# WirelessEarBuds_Amp.net
KiCad netlist of a schematic drawn in Altium Designer
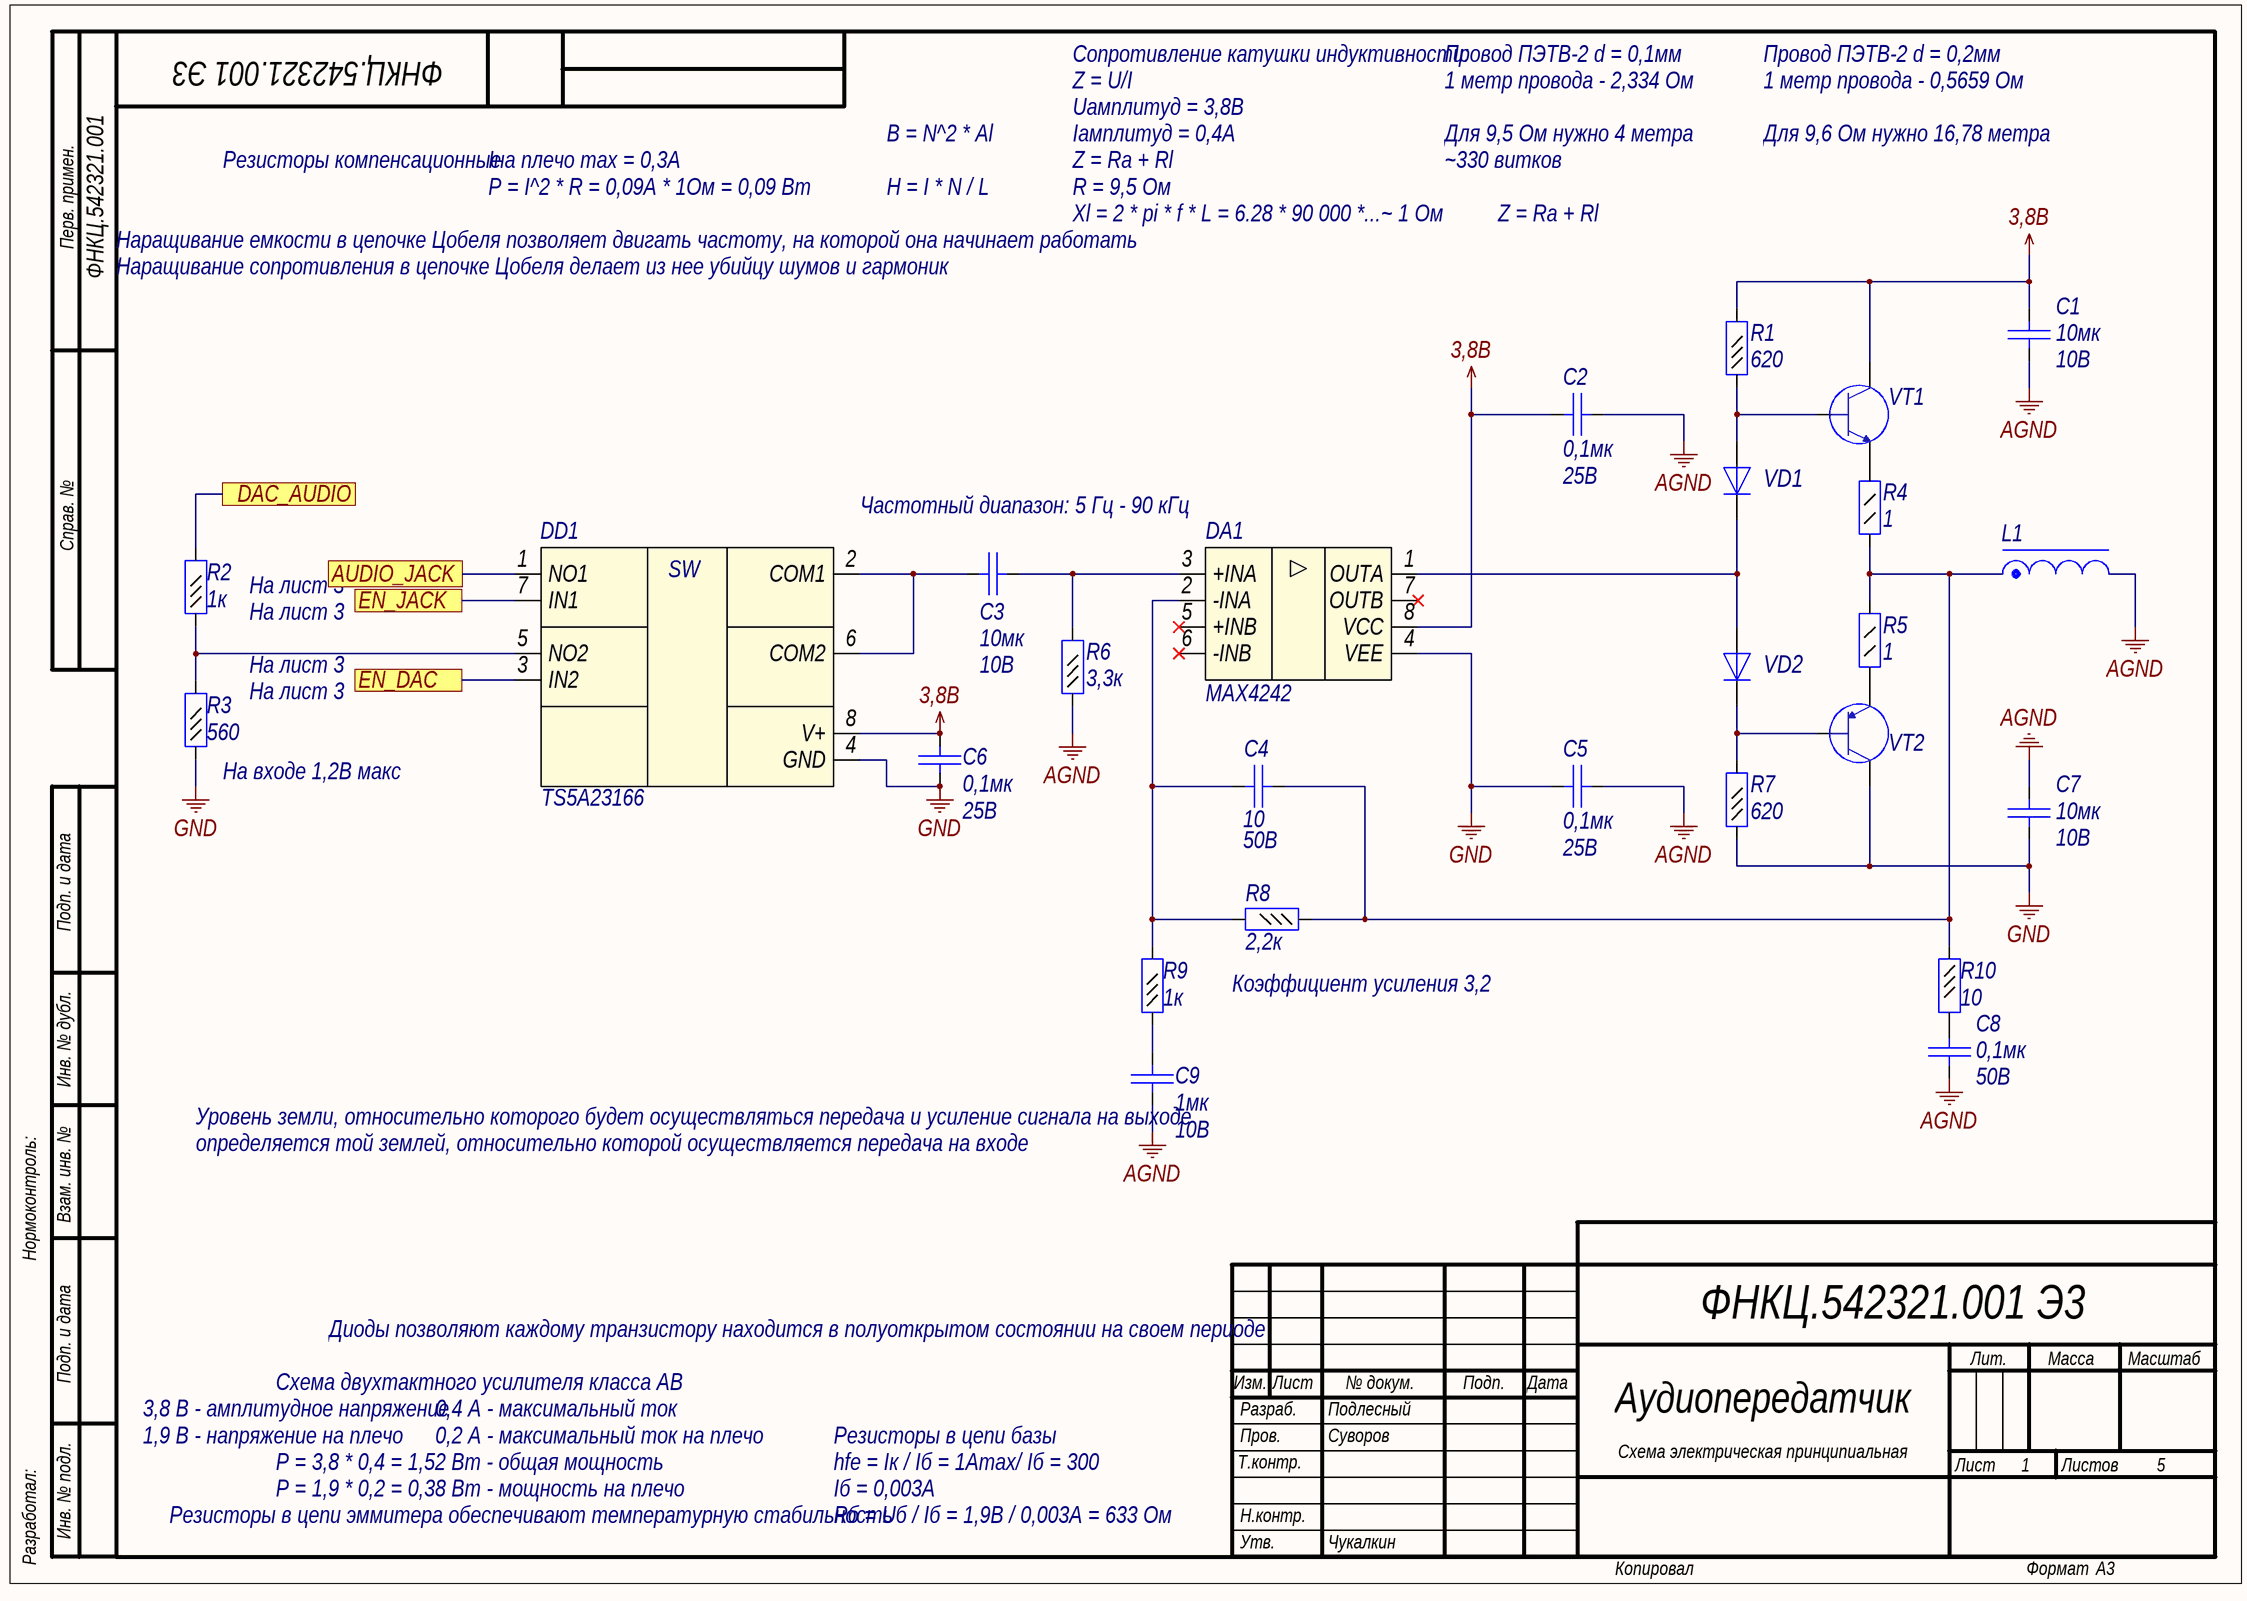
[diagram p0: WirelessEarBuds_Amp.SchDoc]

(export (version "E")
  (design (tool "Eeschema 10.0.6"))
  (components
    (comp (ref "C1")
      (value "10мк")
      (footprint "C0805")
      (description "Конденсатор")
      (fields
        (field (name "VOLTAGE") "10В")
        (field (name "PART NUMBER") "GRM21BR71A106KE51L")
        (field (name "Comment") "Capacitor")
      )
      (libsource (lib "MOP44") (part "Capacitor"))
    )
    (comp (ref "C2")
      (value "0,1мк")
      (footprint "C0402")
      (description "Конденсатор")
      (fields
        (field (name "VOLTAGE") "25B")
        (field (name "PART NUMBER") "GRM155F51E104Z**")
        (field (name "Comment") "Capacitor")
      )
      (libsource (lib "MOP44") (part "Capacitor"))
    )
    (comp (ref "C3")
      (value "10мк")
      (footprint "C0805")
      (description "Конденсатор")
      (fields
        (field (name "VOLTAGE") "10В")
        (field (name "PART NUMBER") "GRM21BR71A106KE51L")
        (field (name "Comment") "Capacitor")
      )
      (libsource (lib "MOP44") (part "Capacitor"))
    )
    (comp (ref "C4")
      (value "10")
      (footprint "C0402")
      (description "Конденсатор")
      (fields
        (field (name "VOLTAGE") "50B")
        (field (name "PART NUMBER") "GRM1535C1H100J")
        (field (name "Comment") "Capacitor")
      )
      (libsource (lib "MOP44") (part "Capacitor"))
    )
    (comp (ref "C5")
      (value "0,1мк")
      (footprint "C0402")
      (description "Конденсатор")
      (fields
        (field (name "VOLTAGE") "25B")
        (field (name "PART NUMBER") "GRM155F51E104Z**")
        (field (name "Comment") "Capacitor")
      )
      (libsource (lib "MOP44") (part "Capacitor"))
    )
    (comp (ref "C6")
      (value "0,1мк")
      (footprint "C0402")
      (description "Конденсатор")
      (fields
        (field (name "VOLTAGE") "25B")
        (field (name "PART NUMBER") "GRM155F51E104Z**")
        (field (name "Comment") "Capacitor")
      )
      (libsource (lib "MOP44") (part "Capacitor"))
    )
    (comp (ref "C7")
      (value "10мк")
      (footprint "C0805")
      (description "Конденсатор")
      (fields
        (field (name "VOLTAGE") "10В")
        (field (name "PART NUMBER") "GRM21BR71A106KE51L")
        (field (name "Comment") "Capacitor")
      )
      (libsource (lib "MOP44") (part "Capacitor"))
    )
    (comp (ref "C8")
      (value "0,1мк")
      (footprint "C0402")
      (description "Конденсатор")
      (fields
        (field (name "VOLTAGE") "50B")
        (field (name "PART NUMBER") "GRM1535C1H100J")
        (field (name "Comment") "Capacitor")
      )
      (libsource (lib "MOP44") (part "Capacitor"))
    )
    (comp (ref "C9")
      (value "1мк")
      (footprint "C0402")
      (description "Конденсатор")
      (fields
        (field (name "VOLTAGE") "10B")
        (field (name "PART NUMBER") "GRM155R61A105K")
        (field (name "Comment") "Capacitor")
      )
      (libsource (lib "MOP44") (part "Capacitor"))
    )
    (comp (ref "DA1")
      (value "MAX4242")
      (footprint "8µMAX")
      (description "МИКРОМОЩНЫЙ Single/Dual/Quad, +1.8V/10µA, SOT23,  Beyond-the-Rails Op Amps")
      (fields (field (name "PART NUMBER") "MAX4242EUA"))
      (libsource (lib "MOP44") (part "MAX4242"))
    )
    (comp (ref "DD1")
      (value "TS5A23166")
      (footprint "US8")
      (description "Dual-SPST Analog Switch")
      (libsource (lib "MOP44") (part "TS5A23166"))
    )
    (comp (ref "L1")
      (value "InductorSerd")
      (footprint "InductorPetlya")
      (description "EMI Suppression Filter")
      (libsource (lib "MOP44") (part "InductorSerd"))
    )
    (comp (ref "R1")
      (value "620")
      (footprint "R0402")
      (description "Резистор")
      (fields (field (name "PART NUMBER") "RC0402FR-07620RL") (field (name "POWER") "0,062Вт"))
      (libsource (lib "MOP44") (part "Resistor_0,062Вт"))
    )
    (comp (ref "R2")
      (value "1к")
      (footprint "R0402")
      (description "Резистор")
      (fields (field (name "PART NUMBER") "RC0402FR-072K3") (field (name "POWER") "0,062Вт"))
      (libsource (lib "MOP44") (part "Resistor_0,062Вт"))
    )
    (comp (ref "R3")
      (value "560")
      (footprint "R0402")
      (description "Резистор")
      (fields (field (name "PART NUMBER") "RC0402FR-072K3") (field (name "POWER") "0,062Вт"))
      (libsource (lib "MOP44") (part "Resistor_0,062Вт"))
    )
    (comp (ref "R4")
      (value "1")
      (footprint "R0805")
      (description "Резистор")
      (fields (field (name "PART NUMBER") "RC0805FR-071RL") (field (name "POWER") "0,125Вт"))
      (libsource (lib "MOP44") (part "Resistor_0,125Вт"))
    )
    (comp (ref "R5")
      (value "1")
      (footprint "R0805")
      (description "Резистор")
      (fields (field (name "PART NUMBER") "RC0805FR-071RL") (field (name "POWER") "0,125Вт"))
      (libsource (lib "MOP44") (part "Resistor_0,125Вт"))
    )
    (comp (ref "R6")
      (value "3,3к")
      (footprint "R0402")
      (description "Резистор")
      (fields (field (name "PART NUMBER") "RC0402FR-072K3") (field (name "POWER") "0,062Вт"))
      (libsource (lib "MOP44") (part "Resistor_0,062Вт"))
    )
    (comp (ref "R7")
      (value "620")
      (footprint "R0402")
      (description "Резистор")
      (fields (field (name "PART NUMBER") "RC0402FR-07620RL") (field (name "POWER") "0,062Вт"))
      (libsource (lib "MOP44") (part "Resistor_0,062Вт"))
    )
    (comp (ref "R8")
      (value "2,2к")
      (footprint "R0402")
      (description "Резистор")
      (fields (field (name "PART NUMBER") "RC0402FR-072K3") (field (name "POWER") "0,062Вт"))
      (libsource (lib "") (part "Resistor_0,062Вт_1"))
    )
    (comp (ref "R9")
      (value "1к")
      (footprint "R0402")
      (description "Резистор")
      (fields (field (name "PART NUMBER") "RC0402FR-072K3") (field (name "POWER") "0,062Вт"))
      (libsource (lib "MOP44") (part "Resistor_0,062Вт"))
    )
    (comp (ref "R10")
      (value "10")
      (footprint "R0402")
      (description "Резистор")
      (fields (field (name "PART NUMBER") "RC0402FR-072K3") (field (name "POWER") "0,062Вт"))
      (libsource (lib "") (part "Resistor_0,062Вт_2"))
    )
    (comp (ref "VD1")
      (value "Diode")
      (footprint "SOD-323")
      (description "Диод")
      (fields (field (name "PART NUMBER") "BAS321.115"))
      (libsource (lib "MOP44") (part "Diode"))
    )
    (comp (ref "VD2")
      (value "Diode")
      (footprint "SOD-323")
      (description "Диод")
      (fields (field (name "PART NUMBER") "BAS321.115"))
      (libsource (lib "MOP44") (part "Diode"))
    )
    (comp (ref "VT1")
      (value "BJT NPN")
      (footprint "SOT-223")
      (fields (field (name "POWER") "2Вт") (field (name "PART NUMBER") "PBSS4540Z.115"))
      (libsource (lib "MOP44") (part "BJT NPN"))
    )
    (comp (ref "VT2")
      (value "BJT PNP")
      (footprint "SOT-223")
      (fields (field (name "POWER") "2Вт") (field (name "PART NUMBER") "PBSS5540Z.115"))
      (libsource (lib "MOP44") (part "BJT PNP"))
    )
  )
  (nets
    (net (code "1") (name "/AUDIO_JACK") (class "Default")
      (node (ref "DD1") (pin "1") (pinfunction "NO1_1") (pintype "power_in"))
    )
    (net (code "2") (name "/DAC_AUDIO") (class "Default")
      (node (ref "R2") (pin "2") (pinfunction "2_2") (pintype "passive"))
    )
    (net (code "3") (name "/EN_DAC") (class "Default")
      (node (ref "DD1") (pin "3") (pinfunction "IN2_3") (pintype "power_in"))
    )
    (net (code "4") (name "/EN_JACK") (class "Default")
      (node (ref "DD1") (pin "7") (pinfunction "IN1_7") (pintype "power_in"))
    )
    (net (code "5") (name "3,8B") (class "Default")
      (node (ref "C1") (pin "2") (pinfunction "2_2") (pintype "passive"))
      (node (ref "C2") (pin "2") (pinfunction "2_2") (pintype "passive"))
      (node (ref "C6") (pin "1") (pinfunction "1_1") (pintype "passive"))
      (node (ref "DA1") (pin "8") (pinfunction "VCC_8") (pintype "passive"))
      (node (ref "DD1") (pin "8") (pinfunction "V+_8") (pintype "power_in"))
      (node (ref "R1") (pin "2") (pinfunction "2_2") (pintype "passive"))
      (node (ref "VT1") (pin "2") (pinfunction "2_2") (pintype "passive"))
    )
    (net (code "6") (name "AGND") (class "Default")
      (node (ref "C1") (pin "1") (pinfunction "1_1") (pintype "passive"))
      (node (ref "C2") (pin "1") (pinfunction "1_1") (pintype "passive"))
      (node (ref "C5") (pin "1") (pinfunction "1_1") (pintype "passive"))
      (node (ref "C7") (pin "2") (pinfunction "2_2") (pintype "passive"))
      (node (ref "C8") (pin "1") (pinfunction "1_1") (pintype "passive"))
      (node (ref "C9") (pin "1") (pinfunction "1_1") (pintype "passive"))
      (node (ref "L1") (pin "2") (pinfunction "2_2") (pintype "passive"))
      (node (ref "R6") (pin "1") (pinfunction "1_1") (pintype "passive"))
    )
    (net (code "7") (name "GND") (class "Default")
      (node (ref "C5") (pin "2") (pinfunction "2_2") (pintype "passive"))
      (node (ref "C6") (pin "2") (pinfunction "2_2") (pintype "passive"))
      (node (ref "C7") (pin "1") (pinfunction "1_1") (pintype "passive"))
      (node (ref "DA1") (pin "4") (pinfunction "VEE_4") (pintype "passive"))
      (node (ref "DD1") (pin "4") (pinfunction "GND_4") (pintype "power_in"))
      (node (ref "R3") (pin "1") (pinfunction "1_1") (pintype "passive"))
      (node (ref "R7") (pin "1") (pinfunction "1_1") (pintype "passive"))
      (node (ref "VT2") (pin "2") (pinfunction "2_2") (pintype "passive"))
    )
    (net (code "8") (name "Net-(C4-Pad2)") (class "Default")
      (node (ref "C4") (pin "2") (pinfunction "2_2") (pintype "passive"))
      (node (ref "L1") (pin "1") (pinfunction "1_1") (pintype "passive"))
      (node (ref "R10") (pin "1") (pinfunction "1_1") (pintype "passive"))
      (node (ref "R4") (pin "1") (pinfunction "1_1") (pintype "passive"))
      (node (ref "R5") (pin "2") (pinfunction "2_2") (pintype "passive"))
      (node (ref "R8") (pin "1") (pinfunction "1_1") (pintype "passive"))
    )
    (net (code "9") (name "Net-(C8-Pad2)") (class "Default")
      (node (ref "C8") (pin "2") (pinfunction "2_2") (pintype "passive"))
      (node (ref "R10") (pin "2") (pinfunction "2_2") (pintype "passive"))
    )
    (net (code "10") (name "Net-(C9-Pad2)") (class "Default")
      (node (ref "C9") (pin "2") (pinfunction "2_2") (pintype "passive"))
      (node (ref "R9") (pin "1") (pinfunction "1_1") (pintype "passive"))
    )
    (net (code "11") (name "Net-(DA1-+INA)") (class "Default")
      (node (ref "C3") (pin "2") (pinfunction "2_2") (pintype "passive"))
      (node (ref "DA1") (pin "3") (pinfunction "+INA_3") (pintype "passive"))
      (node (ref "R6") (pin "2") (pinfunction "2_2") (pintype "passive"))
    )
    (net (code "12") (name "Net-(DA1--INA)") (class "Default")
      (node (ref "C4") (pin "1") (pinfunction "1_1") (pintype "passive"))
      (node (ref "DA1") (pin "2") (pinfunction "-INA_2") (pintype "passive"))
      (node (ref "R8") (pin "2") (pinfunction "2_2") (pintype "passive"))
      (node (ref "R9") (pin "2") (pinfunction "2_2") (pintype "passive"))
    )
    (net (code "13") (name "Net-(DA1-OUTA)") (class "Default")
      (node (ref "DA1") (pin "1") (pinfunction "OUTA_1") (pintype "passive"))
      (node (ref "VD1") (pin "1") (pinfunction "K_1") (pintype "passive"))
      (node (ref "VD2") (pin "2") (pinfunction "A_2") (pintype "passive"))
    )
    (net (code "14") (name "Net-(DD1-COM1)") (class "Default")
      (node (ref "C3") (pin "1") (pinfunction "1_1") (pintype "passive"))
      (node (ref "DD1") (pin "2") (pinfunction "COM1_2") (pintype "power_in"))
      (node (ref "DD1") (pin "6") (pinfunction "COM2_6") (pintype "power_in"))
    )
    (net (code "15") (name "Net-(DD1-NO2)") (class "Default")
      (node (ref "DD1") (pin "5") (pinfunction "NO2_5") (pintype "power_in"))
      (node (ref "R2") (pin "1") (pinfunction "1_1") (pintype "passive"))
      (node (ref "R3") (pin "2") (pinfunction "2_2") (pintype "passive"))
    )
    (net (code "16") (name "Net-(R4-Pad2)") (class "Default")
      (node (ref "R4") (pin "2") (pinfunction "2_2") (pintype "passive"))
      (node (ref "VT1") (pin "3") (pinfunction "3_3") (pintype "passive"))
    )
    (net (code "17") (name "Net-(R5-Pad1)") (class "Default")
      (node (ref "R5") (pin "1") (pinfunction "1_1") (pintype "passive"))
      (node (ref "VT2") (pin "3") (pinfunction "3_3") (pintype "passive"))
    )
    (net (code "18") (name "Net-(VD1-A)") (class "Default")
      (node (ref "R1") (pin "1") (pinfunction "1_1") (pintype "passive"))
      (node (ref "VD1") (pin "2") (pinfunction "A_2") (pintype "passive"))
      (node (ref "VT1") (pin "1") (pinfunction "1_1") (pintype "passive"))
    )
    (net (code "19") (name "Net-(VD2-K)") (class "Default")
      (node (ref "R7") (pin "2") (pinfunction "2_2") (pintype "passive"))
      (node (ref "VD2") (pin "1") (pinfunction "K_1") (pintype "passive"))
      (node (ref "VT2") (pin "1") (pinfunction "1_1") (pintype "passive"))
    )
    (net (code "20") (name "unconnected-(DA1-+INB-Pad5)") (class "Default")
      (node (ref "DA1") (pin "5") (pinfunction "+INB_5") (pintype "passive+no_connect"))
    )
    (net (code "21") (name "unconnected-(DA1--INB-Pad6)") (class "Default")
      (node (ref "DA1") (pin "6") (pinfunction "-INB_6") (pintype "passive+no_connect"))
    )
    (net (code "22") (name "unconnected-(DA1-OUTB-Pad7)") (class "Default")
      (node (ref "DA1") (pin "7") (pinfunction "OUTB_7") (pintype "passive+no_connect"))
    )
  )
)
